# B_D-A_Power.net
KiCad netlist of a schematic drawn in Altium Designer
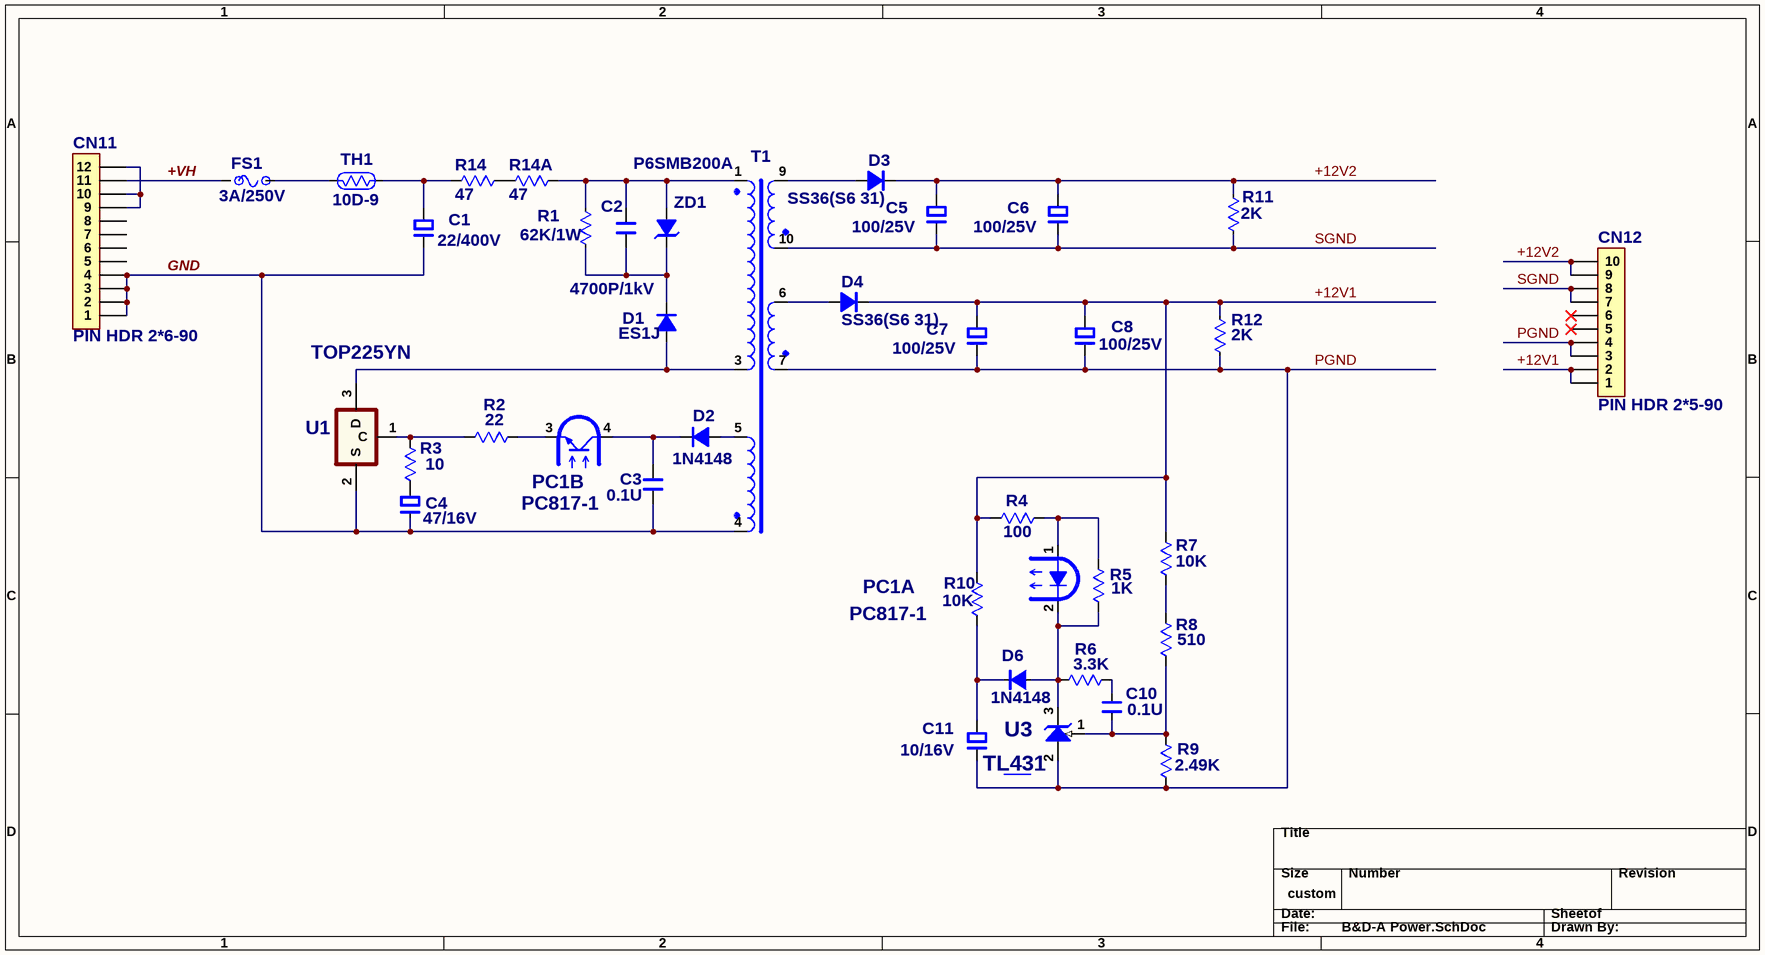
[diagram p0: B&D-A Power.SchDoc]

(export (version "E")
  (design (tool "Eeschema 10.0.6"))
  (components
    (comp (ref "C1")
      (value "22/400V")
      (footprint "CAP P D12.8/5.08")
      (description "Electrolytic Capacitor")
      (libsource (lib "*") (part "CAP P_3"))
    )
    (comp (ref "C2")
      (value "4700P/1kV")
      (footprint "CAP 7.0*3.5/5.08")
      (description "Capacitor")
      (libsource (lib "*") (part "CAP_3"))
    )
    (comp (ref "C3")
      (value "0.1U")
      (footprint "2012(0805)-2.54")
      (description "Capacitor")
      (libsource (lib "*") (part "CAP_3"))
    )
    (comp (ref "C4")
      (value "47/16V")
      (footprint "CAP P D8.2/3.56")
      (description "Electrolytic Capacitor")
      (libsource (lib "*") (part "CAP P_2"))
    )
    (comp (ref "C5")
      (value "100/25V")
      (footprint "CAP P D6.4/3.05")
      (description "Electrolytic Capacitor")
      (libsource (lib "*") (part "CAP P_3"))
    )
    (comp (ref "C6")
      (value "100/25V")
      (footprint "CAP P D6.4/3.05")
      (description "Electrolytic Capacitor")
      (libsource (lib "*") (part "CAP P_3"))
    )
    (comp (ref "C7")
      (value "100/25V")
      (footprint "CAP P D6.4/3.05")
      (description "Electrolytic Capacitor")
      (libsource (lib "*") (part "CAP P_3"))
    )
    (comp (ref "C8")
      (value "100/25V")
      (footprint "CAP P D6.4/3.05")
      (description "Electrolytic Capacitor")
      (libsource (lib "*") (part "CAP P_3"))
    )
    (comp (ref "C10")
      (value "0.1U")
      (footprint "2012(0805)-2.54")
      (description "Capacitor")
      (libsource (lib "*") (part "CAP_2"))
    )
    (comp (ref "C11")
      (value "10/16V")
      (footprint "CAP P 3528")
      (description "Electrolytic Capacitor")
      (libsource (lib "*") (part "CAP P3_V.3"))
    )
    (comp (ref "CN11")
      (value "PIN HDR 2*6-90")
      (footprint "PIN HDR 2*6-90")
      (description "Connector")
      (libsource (lib "*") (part "CON12"))
    )
    (comp (ref "CN12")
      (value "PIN HDR 2*5-90")
      (footprint "PIN HDR 2*5-90")
      (description "Connector")
      (libsource (lib "*") (part "CON10"))
    )
    (comp (ref "D1")
      (value "ES1J")
      (footprint "D5025")
      (description "Diode")
      (libsource (lib "*") (part "DIODE(AK)_2"))
    )
    (comp (ref "D2")
      (value "1N4148")
      (footprint "D3515")
      (description "Diode")
      (libsource (lib "*") (part "DIODE(AK)_2"))
    )
    (comp (ref "D3")
      (value "SS36(S6 31)")
      (footprint "D7060")
      (description "Diode")
      (libsource (lib "*") (part "DIODE(AK)_2"))
    )
    (comp (ref "D4")
      (value "SS36(S6 31)")
      (footprint "D7060")
      (description "Diode")
      (libsource (lib "*") (part "DIODE(AK)_2"))
    )
    (comp (ref "D6")
      (value "1N4148")
      (footprint "D3515")
      (description "Diode")
      (libsource (lib "*") (part "DIODE_1"))
    )
    (comp (ref "FS1")
      (value "3A/250V")
      (footprint "FUSE D8/5.08")
      (description "FUSE")
      (libsource (lib "*") (part "F.S_1"))
    )
    (comp (ref "PC1") (value "PC817-1") (footprint "DIP-4-340") (libsource (lib "*") (part "TLP521-1_2")))
    (comp (ref "R1")
      (value "62K/1W")
      (footprint "RES D3.0/5.08")
      (description "Resistor")
      (libsource (lib "*") (part "RES_1"))
    )
    (comp (ref "R2")
      (value "22")
      (footprint "2012(0805)-2.54")
      (description "Resistor")
      (libsource (lib "*") (part "RES_2"))
    )
    (comp (ref "R3")
      (value "10")
      (footprint "2012(0805)-2.54")
      (description "Resistor")
      (libsource (lib "*") (part "RES_2"))
    )
    (comp (ref "R4")
      (value "100")
      (footprint "2012(0805)-2.54")
      (description "Resistor")
      (libsource (lib "*") (part "RES_2"))
    )
    (comp (ref "R5")
      (value "1K")
      (footprint "2012(0805)-2.54")
      (description "Resistor")
      (libsource (lib "*") (part "RES_2"))
    )
    (comp (ref "R6")
      (value "3.3K")
      (footprint "2012(0805)-2.54")
      (description "Resistor")
      (libsource (lib "*") (part "RES_2"))
    )
    (comp (ref "R7")
      (value "10K")
      (footprint "2012(0805)-2.54")
      (description "Resistor")
      (libsource (lib "*") (part "RES_2"))
    )
    (comp (ref "R8")
      (value "510")
      (footprint "2012(0805)-2.54")
      (description "Resistor")
      (libsource (lib "*") (part "RES_2"))
    )
    (comp (ref "R9")
      (value "2.49K")
      (footprint "2012(0805)-2.54")
      (description "Resistor")
      (libsource (lib "*") (part "RES_2"))
    )
    (comp (ref "R10")
      (value "10K")
      (footprint "2012(0805)-2.54")
      (description "Resistor")
      (libsource (lib "*") (part "RES_2"))
    )
    (comp (ref "R11")
      (value "2K")
      (footprint "2012(0805)-2.54")
      (description "Resistor")
      (libsource (lib "*") (part "RES_1"))
    )
    (comp (ref "R12")
      (value "2K")
      (footprint "2012(0805)-2.54")
      (description "Resistor")
      (libsource (lib "*") (part "RES_1"))
    )
    (comp (ref "R14")
      (value "47")
      (footprint "6432(2512)-6.6")
      (description "Resistor")
      (libsource (lib "*") (part "RES_2"))
    )
    (comp (ref "R14A")
      (value "47")
      (footprint "6432(2512)-6.6")
      (description "Resistor")
      (libsource (lib "*") (part "RES_2"))
    )
    (comp (ref "T1")
      (value "FEE-22-10")
      (footprint "FEE-22-10/10.4*15.7")
      (libsource (lib "*") (part "TRANS8-4_1"))
    )
    (comp (ref "TH1")
      (value "10D-9")
      (footprint "TH 9.4*4/7.62*1.52")
      (description "Thermistor")
      (libsource (lib "*") (part "TH_2"))
    )
    (comp (ref "U1")
      (value "TOP225YN")
      (footprint "TO-220_1")
      (description "3-Terminal Positive Voltage Regulator")
      (libsource (lib "*") (part "TOP100Y_1"))
    )
    (comp (ref "U3")
      (value "TL431")
      (footprint "TO-92_1")
      (description "Programmable Voltage Reference")
      (libsource (lib "*") (part "TL431_2"))
    )
    (comp (ref "ZD1")
      (value "P6SMB200A")
      (footprint "DZ5035")
      (description "Zener Diode")
      (libsource (lib "*") (part "ZD_2"))
    )
  )
  (nets
    (net (code "1") (name "/+12V1") (class "Default")
      (node (ref "C7") (pin "1") (pinfunction "1_1") (pintype "passive"))
      (node (ref "C8") (pin "1") (pinfunction "1_1") (pintype "passive"))
      (node (ref "CN12") (pin "1") (pinfunction "1_1") (pintype "passive"))
      (node (ref "CN12") (pin "2") (pinfunction "2_2") (pintype "passive"))
      (node (ref "D4") (pin "2") (pinfunction "K_2") (pintype "passive"))
      (node (ref "R10") (pin "1") (pinfunction "1_1") (pintype "passive"))
      (node (ref "R12") (pin "2") (pinfunction "2_2") (pintype "passive"))
      (node (ref "R4") (pin "2") (pinfunction "2_2") (pintype "passive"))
      (node (ref "R7") (pin "2") (pinfunction "2_2") (pintype "passive"))
    )
    (net (code "2") (name "/+12V2") (class "Default")
      (node (ref "C5") (pin "1") (pinfunction "1_1") (pintype "passive"))
      (node (ref "C6") (pin "1") (pinfunction "1_1") (pintype "passive"))
      (node (ref "CN12") (pin "10") (pinfunction "10_10") (pintype "passive"))
      (node (ref "CN12") (pin "9") (pinfunction "9_9") (pintype "passive"))
      (node (ref "D3") (pin "2") (pinfunction "K_2") (pintype "passive"))
      (node (ref "R11") (pin "2") (pinfunction "2_2") (pintype "passive"))
    )
    (net (code "3") (name "/+VH") (class "Default")
      (node (ref "CN11") (pin "11") (pinfunction "11_11") (pintype "passive"))
      (node (ref "FS1") (pin "1") (pinfunction "1_1") (pintype "passive"))
    )
    (net (code "4") (name "/GND") (class "Default")
      (node (ref "C1") (pin "2") (pinfunction "2_2") (pintype "passive"))
      (node (ref "C3") (pin "2") (pinfunction "2_2") (pintype "passive"))
      (node (ref "C4") (pin "2") (pinfunction "2_2") (pintype "passive"))
      (node (ref "CN11") (pin "1") (pinfunction "1_1") (pintype "passive"))
      (node (ref "CN11") (pin "2") (pinfunction "2_2") (pintype "passive"))
      (node (ref "CN11") (pin "3") (pinfunction "3_3") (pintype "passive"))
      (node (ref "CN11") (pin "4") (pinfunction "4_4") (pintype "passive"))
      (node (ref "T1") (pin "4") (pinfunction "4_4") (pintype "passive"))
      (node (ref "U1") (pin "2") (pinfunction "S_2") (pintype "passive"))
    )
    (net (code "5") (name "/PGND") (class "Default")
      (node (ref "C11") (pin "2") (pinfunction "2_2") (pintype "passive"))
      (node (ref "C7") (pin "2") (pinfunction "2_2") (pintype "passive"))
      (node (ref "C8") (pin "2") (pinfunction "2_2") (pintype "passive"))
      (node (ref "CN12") (pin "3") (pinfunction "3_3") (pintype "passive"))
      (node (ref "CN12") (pin "4") (pinfunction "4_4") (pintype "passive"))
      (node (ref "R12") (pin "1") (pinfunction "1_1") (pintype "passive"))
      (node (ref "R9") (pin "1") (pinfunction "1_1") (pintype "passive"))
      (node (ref "T1") (pin "7") (pinfunction "7_7") (pintype "passive"))
      (node (ref "U3") (pin "2") (pinfunction "A_2") (pintype "passive"))
    )
    (net (code "6") (name "/SGND") (class "Default")
      (node (ref "C5") (pin "2") (pinfunction "2_2") (pintype "passive"))
      (node (ref "C6") (pin "2") (pinfunction "2_2") (pintype "passive"))
      (node (ref "CN12") (pin "7") (pinfunction "7_7") (pintype "passive"))
      (node (ref "CN12") (pin "8") (pinfunction "8_8") (pintype "passive"))
      (node (ref "R11") (pin "1") (pinfunction "1_1") (pintype "passive"))
      (node (ref "T1") (pin "10") (pinfunction "10_10") (pintype "passive"))
    )
    (net (code "7") (name "Net-(C1-Pad1)") (class "Default")
      (node (ref "C1") (pin "1") (pinfunction "1_1") (pintype "passive"))
      (node (ref "R14") (pin "1") (pinfunction "1_1") (pintype "passive"))
      (node (ref "TH1") (pin "2") (pinfunction "2_2") (pintype "passive"))
    )
    (net (code "8") (name "Net-(C4-Pad1)") (class "Default")
      (node (ref "C4") (pin "1") (pinfunction "1_1") (pintype "passive"))
      (node (ref "R3") (pin "2") (pinfunction "2_2") (pintype "passive"))
    )
    (net (code "9") (name "Net-(C10-Pad1)") (class "Default")
      (node (ref "C10") (pin "1") (pinfunction "1_1") (pintype "passive"))
      (node (ref "R6") (pin "1") (pinfunction "1_1") (pintype "passive"))
    )
    (net (code "10") (name "Net-(CN11-Pad10)") (class "Default")
      (node (ref "CN11") (pin "10") (pinfunction "10_10") (pintype "passive"))
      (node (ref "CN11") (pin "12") (pinfunction "12_12") (pintype "passive"))
      (node (ref "CN11") (pin "9") (pinfunction "9_9") (pintype "passive"))
    )
    (net (code "11") (name "Net-(D1-A)") (class "Default")
      (node (ref "D1") (pin "1") (pinfunction "A_1") (pintype "passive"))
      (node (ref "T1") (pin "3") (pintype "passive"))
      (node (ref "U1") (pin "3") (pinfunction "D_3") (pintype "passive"))
    )
    (net (code "12") (name "Net-(D1-K)") (class "Default")
      (node (ref "C2") (pin "2") (pinfunction "2_2") (pintype "passive"))
      (node (ref "D1") (pin "2") (pinfunction "K_2") (pintype "passive"))
      (node (ref "R1") (pin "2") (pinfunction "2_2") (pintype "passive"))
      (node (ref "ZD1") (pin "2") (pinfunction "K_2") (pintype "passive"))
    )
    (net (code "13") (name "Net-(D2-A)") (class "Default")
      (node (ref "D2") (pin "1") (pinfunction "A_1") (pintype "passive"))
      (node (ref "T1") (pin "5") (pinfunction "5_5") (pintype "passive"))
    )
    (net (code "14") (name "Net-(D2-K)") (class "Default")
      (node (ref "C3") (pin "1") (pinfunction "1_1") (pintype "passive"))
      (node (ref "D2") (pin "2") (pinfunction "K_2") (pintype "passive"))
      (node (ref "PC1") (pin "4") (pinfunction "C_4") (pintype "passive"))
    )
    (net (code "15") (name "Net-(D3-A)") (class "Default")
      (node (ref "D3") (pin "1") (pinfunction "A_1") (pintype "passive"))
      (node (ref "T1") (pin "9") (pinfunction "9_9") (pintype "passive"))
    )
    (net (code "16") (name "Net-(D4-A)") (class "Default")
      (node (ref "D4") (pin "1") (pinfunction "A_1") (pintype "passive"))
      (node (ref "T1") (pin "6") (pinfunction "6_6") (pintype "passive"))
    )
    (net (code "17") (name "Net-(D6-A)") (class "Default")
      (node (ref "D6") (pin "1") (pinfunction "A_1") (pintype "passive"))
      (node (ref "PC1") (pin "2") (pinfunction "K_2") (pintype "passive"))
      (node (ref "R5") (pin "1") (pinfunction "1_1") (pintype "passive"))
      (node (ref "R6") (pin "2") (pinfunction "2_2") (pintype "passive"))
      (node (ref "U3") (pin "3") (pinfunction "K_3") (pintype "passive"))
    )
    (net (code "18") (name "Net-(D6-K)") (class "Default")
      (node (ref "C11") (pin "1") (pinfunction "1_1") (pintype "passive"))
      (node (ref "D6") (pin "2") (pinfunction "K_2") (pintype "passive"))
      (node (ref "R10") (pin "2") (pinfunction "2_2") (pintype "passive"))
    )
    (net (code "19") (name "Net-(FS1-Pad2)") (class "Default")
      (node (ref "FS1") (pin "2") (pinfunction "2_2") (pintype "passive"))
      (node (ref "TH1") (pin "1") (pinfunction "1_1") (pintype "passive"))
    )
    (net (code "20") (name "Net-(PC1A-A)") (class "Default")
      (node (ref "PC1") (pin "1") (pinfunction "A_1") (pintype "passive"))
      (node (ref "R4") (pin "1") (pinfunction "1_1") (pintype "passive"))
      (node (ref "R5") (pin "2") (pinfunction "2_2") (pintype "passive"))
    )
    (net (code "21") (name "Net-(PC1B-E)") (class "Default")
      (node (ref "PC1") (pin "3") (pinfunction "E_3") (pintype "passive"))
      (node (ref "R2") (pin "1") (pinfunction "1_1") (pintype "passive"))
    )
    (net (code "22") (name "Net-(R7-Pad1)") (class "Default")
      (node (ref "R7") (pin "1") (pinfunction "1_1") (pintype "passive"))
      (node (ref "R8") (pin "2") (pinfunction "2_2") (pintype "passive"))
    )
    (net (code "23") (name "Net-(R14-Pad2)") (class "Default")
      (node (ref "R14") (pin "2") (pinfunction "2_2") (pintype "passive"))
      (node (ref "R14A") (pin "1") (pinfunction "1_1") (pintype "passive"))
    )
    (net (code "24") (name "Net-(U1-C)") (class "Default")
      (node (ref "R2") (pin "2") (pinfunction "2_2") (pintype "passive"))
      (node (ref "R3") (pin "1") (pinfunction "1_1") (pintype "passive"))
      (node (ref "U1") (pin "1") (pinfunction "C_1") (pintype "passive"))
    )
    (net (code "25") (name "Net-(U3-R)") (class "Default")
      (node (ref "C10") (pin "2") (pinfunction "2_2") (pintype "passive"))
      (node (ref "R8") (pin "1") (pinfunction "1_1") (pintype "passive"))
      (node (ref "R9") (pin "2") (pinfunction "2_2") (pintype "passive"))
      (node (ref "U3") (pin "1") (pinfunction "R_1") (pintype "input"))
    )
    (net (code "26") (name "Net-(ZD1-A)") (class "Default")
      (node (ref "C2") (pin "1") (pinfunction "1_1") (pintype "passive"))
      (node (ref "R1") (pin "1") (pinfunction "1_1") (pintype "passive"))
      (node (ref "R14A") (pin "2") (pinfunction "2_2") (pintype "passive"))
      (node (ref "T1") (pin "1") (pinfunction "1_1") (pintype "passive"))
      (node (ref "ZD1") (pin "1") (pinfunction "A_1") (pintype "passive"))
    )
    (net (code "27") (name "unconnected-(CN11-Pad5)") (class "Default")
      (node (ref "CN11") (pin "5") (pinfunction "5_5") (pintype "passive"))
    )
    (net (code "28") (name "unconnected-(CN11-Pad6)") (class "Default")
      (node (ref "CN11") (pin "6") (pinfunction "6_6") (pintype "passive"))
    )
    (net (code "29") (name "unconnected-(CN11-Pad7)") (class "Default")
      (node (ref "CN11") (pin "7") (pinfunction "7_7") (pintype "passive"))
    )
    (net (code "30") (name "unconnected-(CN11-Pad8)") (class "Default")
      (node (ref "CN11") (pin "8") (pinfunction "8_8") (pintype "passive"))
    )
    (net (code "31") (name "unconnected-(CN12-Pad5)") (class "Default")
      (node (ref "CN12") (pin "5") (pinfunction "5_5") (pintype "passive+no_connect"))
    )
    (net (code "32") (name "unconnected-(CN12-Pad6)") (class "Default")
      (node (ref "CN12") (pin "6") (pinfunction "6_6") (pintype "passive+no_connect"))
    )
  )
)
